# SCH_power_LED_2026-05-29.net
KiCad netlist of a schematic drawn in EasyEDA
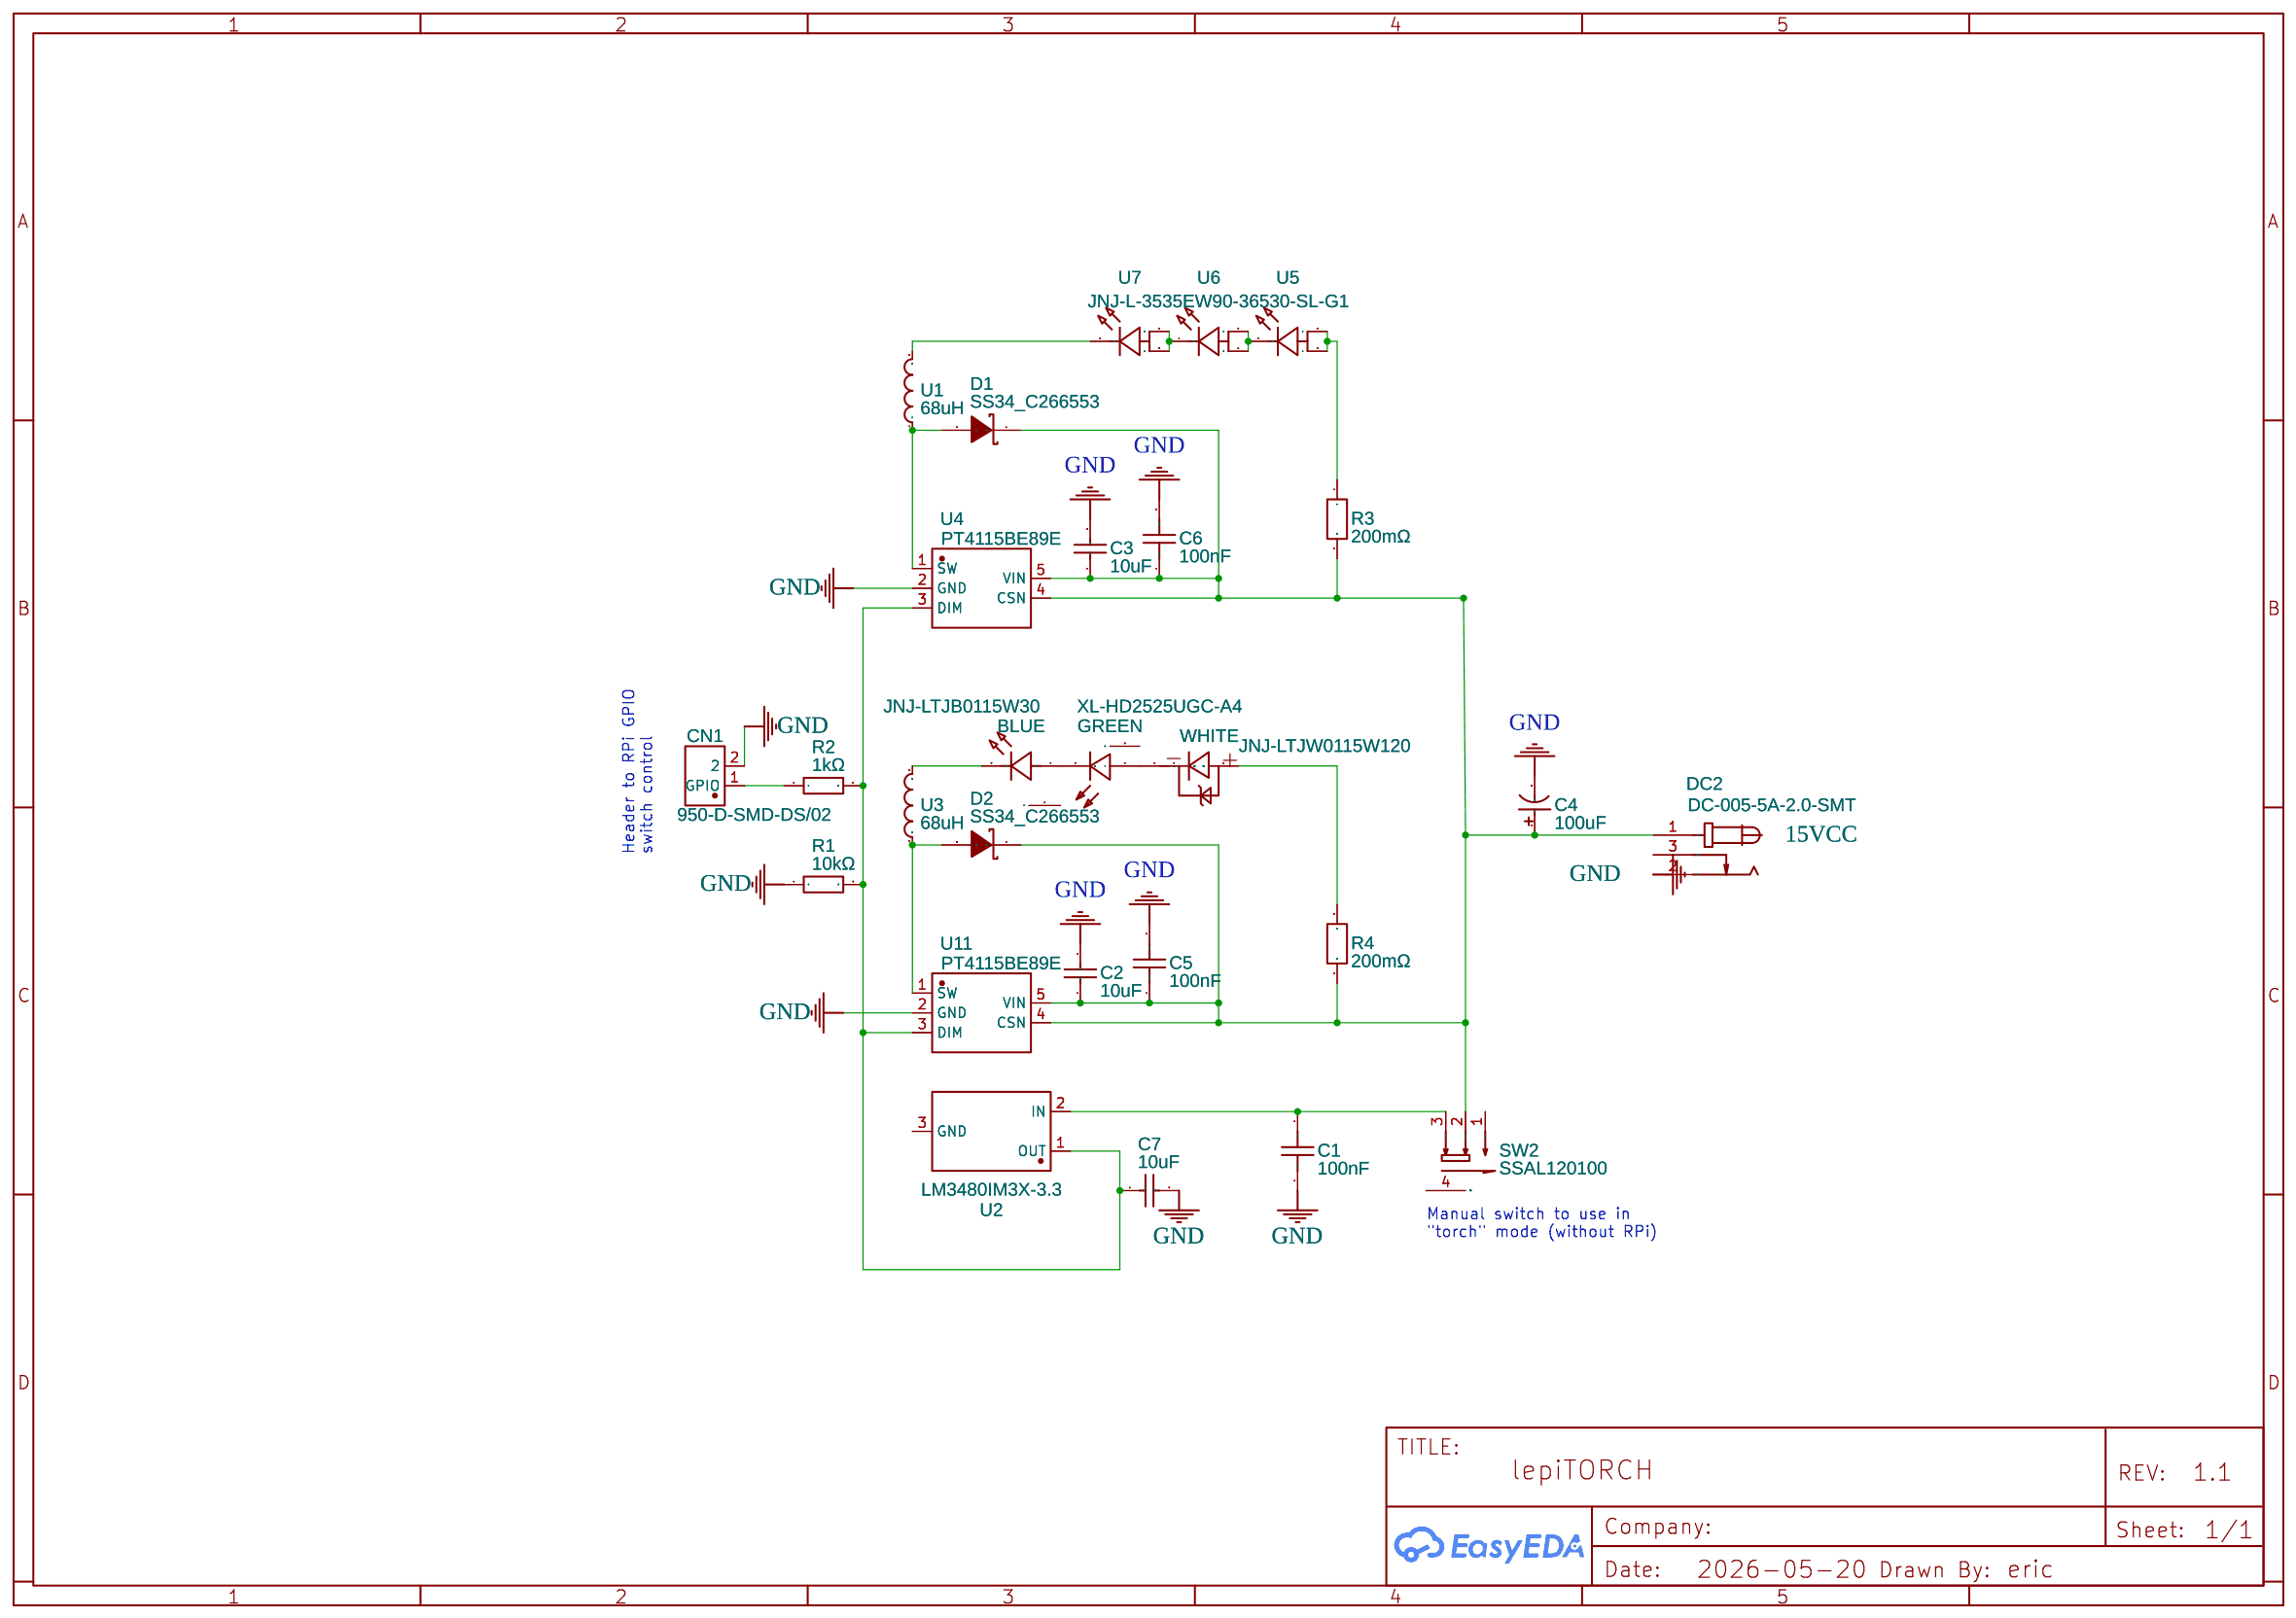
[diagram p0: schematic sheet]

(export (version "E")
  (design (tool "Eeschema 10.0.6"))
  (components
    (comp (ref "BLUE")
      (value "JNJ-LTJB0115W30")
      (fields
        (field (name "Manufacturer Part") "JNJ-LTJB0115W30/56mil/450-460nm")
        (field (name "Manufacturer") "JNJOPTO(强生光电)")
      )
      (libsource (lib "") (part "JNJ-LTJB0115W30/56MIL/450-460NM"))
    )
    (comp (ref "C1")
      (value "100nF")
      (fields (field (name "Manufacturer Part") "GMC04X7R104K25NT") (field (name "Manufacturer") "CAL-CHIP"))
      (libsource (lib "") (part "GMC04X7R104K25NT"))
    )
    (comp (ref "C2")
      (value "10uF")
      (fields
        (field (name "Manufacturer Part") "GRM31CR71E106KA12L")
        (field (name "Manufacturer") "muRata(村田)")
      )
      (libsource (lib "") (part "GRM31CR71E106KA12L"))
    )
    (comp (ref "C3")
      (value "10uF")
      (fields
        (field (name "Manufacturer Part") "GRM31CR71E106KA12L")
        (field (name "Manufacturer") "muRata(村田)")
      )
      (libsource (lib "") (part "GRM31CR71E106KA12L"))
    )
    (comp (ref "C4")
      (value "100uF")
      (fields (field (name "Manufacturer Part") "RVT1E101M0607") (field (name "Manufacturer") "HONOR(荣誉)"))
      (libsource (lib "") (part "RVT1E101M0607"))
    )
    (comp (ref "C5")
      (value "100nF")
      (fields (field (name "Manufacturer Part") "GMC04X7R104K25NT") (field (name "Manufacturer") "CAL-CHIP"))
      (libsource (lib "") (part "GMC04X7R104K25NT"))
    )
    (comp (ref "C6")
      (value "100nF")
      (fields (field (name "Manufacturer Part") "GMC04X7R104K25NT") (field (name "Manufacturer") "CAL-CHIP"))
      (libsource (lib "") (part "GMC04X7R104K25NT"))
    )
    (comp (ref "C7")
      (value "10uF")
      (fields
        (field (name "Manufacturer Part") "GRM31CR71E106KA12L")
        (field (name "Manufacturer") "muRata(村田)")
      )
      (libsource (lib "") (part "GRM31CR71E106KA12L_1"))
    )
    (comp (ref "CN1")
      (value "950-D-SMD-DS/02")
      (fields (field (name "Manufacturer") "WECO(威克德诺)"))
      (libsource (lib "") (part "950-D-SMD-DS/02"))
    )
    (comp (ref "D1")
      (value "SS34_C266553")
      (fields (field (name "Manufacturer Part") "SS34") (field (name "Manufacturer") "BORN(伯恩半导体)"))
      (libsource (lib "") (part "SS34_C266553"))
    )
    (comp (ref "D2")
      (value "SS34_C266553")
      (fields (field (name "Manufacturer Part") "SS34") (field (name "Manufacturer") "BORN(伯恩半导体)"))
      (libsource (lib "") (part "SS34_C266553"))
    )
    (comp (ref "DC2")
      (value "DC-005-5A-2.0-SMT")
      (fields (field (name "Manufacturer") "XKB Connection(中国星坤)"))
      (libsource (lib "") (part "DC-005-5A-2.0-SMT"))
    )
    (comp (ref "GREEN")
      (value "XL-HD2525UGC-A4")
      (fields (field (name "Manufacturer") "XINGLIGHT(成兴光)"))
      (libsource (lib "") (part "XL-HD2525UGC-A4"))
    )
    (comp (ref "R1")
      (value "10kΩ")
      (fields
        (field (name "Manufacturer Part") "TR0402D10K0Q1025Z")
        (field (name "Manufacturer") "EVER OHMS(天二科技)")
      )
      (libsource (lib "") (part "TR0402D10KQ1025"))
    )
    (comp (ref "R2")
      (value "1kΩ")
      (fields
        (field (name "Manufacturer Part") "QR0402F1K00Q10Z")
        (field (name "Manufacturer") "EVER OHMS(天二科技)")
      )
      (libsource (lib "") (part "QR0402F1KQ10"))
    )
    (comp (ref "R3")
      (value "200mΩ")
      (fields (field (name "Manufacturer Part") "FRL0603FR200TS") (field (name "Manufacturer") "FOJAN(富捷)"))
      (libsource (lib "") (part "FRL0603FR200TS"))
    )
    (comp (ref "R4")
      (value "200mΩ")
      (fields (field (name "Manufacturer Part") "FRL0603FR200TS") (field (name "Manufacturer") "FOJAN(富捷)"))
      (libsource (lib "") (part "FRL0603FR200TS"))
    )
    (comp (ref "SW2")
      (value "SSAL120100")
      (fields (field (name "Manufacturer") "ALPSALPINE(阿尔卑斯阿尔派)"))
      (libsource (lib "") (part "SSAL120100"))
    )
    (comp (ref "U1")
      (value "68uH")
      (fields (field (name "Manufacturer Part") "CYA0650-68UH") (field (name "Manufacturer") "SHOU HAN(首韩)"))
      (libsource (lib "") (part "CYA0650-68UH"))
    )
    (comp (ref "U2")
      (value "LM3480IM3X-3.3")
      (fields (field (name "Manufacturer") "TI(德州仪器)"))
      (libsource (lib "") (part "LM3480IM3X-3.3"))
    )
    (comp (ref "U3")
      (value "68uH")
      (fields (field (name "Manufacturer Part") "CYA0650-68UH") (field (name "Manufacturer") "SHOU HAN(首韩)"))
      (libsource (lib "") (part "CYA0650-68UH"))
    )
    (comp (ref "U4")
      (value "PT4115BE89E")
      (fields (field (name "Manufacturer") "PowTech(华润矽威)"))
      (libsource (lib "") (part "PT4115BE89E"))
    )
    (comp (ref "U5")
      (value "JNJ-L-3535EW90-36530-SL-G1")
      (fields (field (name "Manufacturer") "JNJOPTO(强生光电)"))
      (libsource (lib "") (part "JNJ-L-3535EW90-36530-SL-G1"))
    )
    (comp (ref "U6")
      (value "JNJ-L-3535EW90-36530-SL-G1")
      (fields (field (name "Manufacturer") "JNJOPTO(强生光电)"))
      (libsource (lib "") (part "JNJ-L-3535EW90-36530-SL-G1"))
    )
    (comp (ref "U7")
      (value "JNJ-L-3535EW90-36530-SL-G1")
      (fields (field (name "Manufacturer") "JNJOPTO(强生光电)"))
      (libsource (lib "") (part "JNJ-L-3535EW90-36530-SL-G1"))
    )
    (comp (ref "U11")
      (value "PT4115BE89E")
      (fields (field (name "Manufacturer") "PowTech(华润矽威)"))
      (libsource (lib "") (part "PT4115BE89E"))
    )
    (comp (ref "WHITE")
      (value "JNJ-LTJW0115W120")
      (fields
        (field (name "Manufacturer Part") "JNJ-LTJW0115W120/63MIL/6500-7000K")
        (field (name "Manufacturer") "JNJOPTO(强生光电)")
      )
      (libsource (lib "") (part "JNJ-LTJW0115W120/63MIL/6500-7000K"))
    )
  )
  (nets
    (net (code "2") (name "GND") (class "Default")
      (node (ref "C1") (pin "1") (pinfunction "1_1") (pintype "unspecified"))
      (node (ref "C2") (pin "2") (pinfunction "2_2") (pintype "input"))
      (node (ref "C3") (pin "2") (pinfunction "2_2") (pintype "input"))
      (node (ref "C4") (pin "2") (pinfunction "2_2") (pintype "input"))
      (node (ref "C5") (pin "2") (pinfunction "2_2") (pintype "unspecified"))
      (node (ref "C6") (pin "2") (pinfunction "2_2") (pintype "unspecified"))
      (node (ref "C7") (pin "2") (pinfunction "2_2") (pintype "input"))
      (node (ref "CN1") (pin "2") (pinfunction "2_2") (pintype "unspecified"))
      (node (ref "DC2") (pin "2") (pinfunction "2_2") (pintype "unspecified"))
      (node (ref "R1") (pin "1") (pinfunction "1_1") (pintype "unspecified"))
      (node (ref "U11") (pin "2") (pinfunction "GND_2") (pintype "unspecified"))
      (node (ref "U4") (pin "2") (pinfunction "GND_2") (pintype "unspecified"))
    )
    (net (code "3") (name "Net-(BLUE-K)") (class "Default")
      (node (ref "BLUE") (pin "2") (pinfunction "K_2") (pintype "unspecified"))
      (node (ref "U3") (pin "2") (pinfunction "2_2") (pintype "unspecified"))
    )
    (net (code "4") (name "Net-(CN1-GPIO)") (class "Default")
      (node (ref "CN1") (pin "1") (pinfunction "GPIO_1") (pintype "unspecified"))
      (node (ref "R2") (pin "1") (pinfunction "1_1") (pintype "unspecified"))
    )
    (net (code "5") (name "Net-(D1-A)") (class "Default")
      (node (ref "D1") (pin "2") (pinfunction "A_2") (pintype "unspecified"))
      (node (ref "U1") (pin "1") (pinfunction "1_1") (pintype "unspecified"))
      (node (ref "U4") (pin "1") (pinfunction "SW_1") (pintype "unspecified"))
    )
    (net (code "6") (name "Net-(D1-C)") (class "Default")
      (node (ref "C2") (pin "1") (pinfunction "1_1") (pintype "input"))
      (node (ref "C3") (pin "1") (pinfunction "1_1") (pintype "input"))
      (node (ref "C4") (pin "1") (pinfunction "1_1") (pintype "input"))
      (node (ref "C5") (pin "1") (pinfunction "1_1") (pintype "unspecified"))
      (node (ref "C6") (pin "1") (pinfunction "1_1") (pintype "unspecified"))
      (node (ref "D1") (pin "1") (pinfunction "C_1") (pintype "unspecified"))
      (node (ref "D2") (pin "1") (pinfunction "C_1") (pintype "unspecified"))
      (node (ref "DC2") (pin "1") (pinfunction "1_1") (pintype "unspecified"))
      (node (ref "R3") (pin "2") (pinfunction "2_2") (pintype "unspecified"))
      (node (ref "R4") (pin "2") (pinfunction "2_2") (pintype "unspecified"))
      (node (ref "SW2") (pin "2") (pinfunction "2_2") (pintype "unspecified"))
      (node (ref "U11") (pin "4") (pinfunction "CSN_4") (pintype "unspecified"))
      (node (ref "U11") (pin "5") (pinfunction "VIN_5") (pintype "unspecified"))
      (node (ref "U4") (pin "4") (pinfunction "CSN_4") (pintype "unspecified"))
      (node (ref "U4") (pin "5") (pinfunction "VIN_5") (pintype "unspecified"))
    )
    (net (code "7") (name "Net-(D2-A)") (class "Default")
      (node (ref "D2") (pin "2") (pinfunction "A_2") (pintype "unspecified"))
      (node (ref "U11") (pin "1") (pinfunction "SW_1") (pintype "unspecified"))
      (node (ref "U3") (pin "1") (pinfunction "1_1") (pintype "unspecified"))
    )
    (net (code "8") (name "Net-(GREEN-A)") (class "Default")
      (node (ref "GREEN") (pin "2") (pinfunction "A_2") (pintype "unspecified"))
      (node (ref "WHITE") (pin "1") (pinfunction "Cathode_1") (pintype "unspecified"))
    )
    (net (code "9") (name "Net-(GREEN-C)") (class "Default")
      (node (ref "BLUE") (pin "1") (pinfunction "A_1") (pintype "unspecified"))
      (node (ref "GREEN") (pin "1") (pinfunction "C_1") (pintype "unspecified"))
    )
    (net (code "10") (name "Net-(R3-Pad1)") (class "Default")
      (node (ref "R3") (pin "1") (pinfunction "1_1") (pintype "unspecified"))
      (node (ref "U5") (pin "2") (pinfunction "A_2") (pintype "unspecified"))
      (node (ref "U5") (pin "3") (pinfunction "A_3") (pintype "unspecified"))
    )
    (net (code "11") (name "Net-(U2-IN)") (class "Default")
      (node (ref "C1") (pin "2") (pinfunction "2_2") (pintype "unspecified"))
      (node (ref "SW2") (pin "3") (pinfunction "3_3") (pintype "unspecified"))
      (node (ref "U2") (pin "2") (pinfunction "IN_2") (pintype "unspecified"))
    )
    (net (code "12") (name "Net-(U5-C)") (class "Default")
      (node (ref "U5") (pin "1") (pinfunction "C_1") (pintype "unspecified"))
      (node (ref "U6") (pin "2") (pinfunction "A_2") (pintype "unspecified"))
      (node (ref "U6") (pin "3") (pinfunction "A_3") (pintype "unspecified"))
    )
    (net (code "13") (name "Net-(U6-C)") (class "Default")
      (node (ref "U6") (pin "1") (pinfunction "C_1") (pintype "unspecified"))
      (node (ref "U7") (pin "2") (pinfunction "A_2") (pintype "unspecified"))
      (node (ref "U7") (pin "3") (pinfunction "A_3") (pintype "unspecified"))
    )
    (net (code "14") (name "Net-(U7-C)") (class "Default")
      (node (ref "U1") (pin "2") (pinfunction "2_2") (pintype "unspecified"))
      (node (ref "U7") (pin "1") (pinfunction "C_1") (pintype "unspecified"))
    )
    (net (code "15") (name "Net-(U11-DIM)") (class "Default")
      (node (ref "C7") (pin "1") (pinfunction "1_1") (pintype "input"))
      (node (ref "R1") (pin "2") (pinfunction "2_2") (pintype "unspecified"))
      (node (ref "R2") (pin "2") (pinfunction "2_2") (pintype "unspecified"))
      (node (ref "U11") (pin "3") (pinfunction "DIM_3") (pintype "unspecified"))
      (node (ref "U2") (pin "1") (pinfunction "OUT_1") (pintype "unspecified"))
      (node (ref "U4") (pin "3") (pinfunction "DIM_3") (pintype "unspecified"))
    )
    (net (code "16") (name "Net-(WHITE-Anode)") (class "Default")
      (node (ref "R4") (pin "1") (pinfunction "1_1") (pintype "unspecified"))
      (node (ref "WHITE") (pin "3") (pinfunction "Anode_3") (pintype "unspecified"))
    )
    (net (code "17") (name "unconnected-(BLUE-A-Pad3)") (class "Default")
      (node (ref "BLUE") (pin "3") (pinfunction "A_3") (pintype "unspecified"))
    )
    (net (code "18") (name "unconnected-(DC2-Pad3)") (class "Default")
      (node (ref "DC2") (pin "3") (pinfunction "3_3") (pintype "unspecified"))
    )
    (net (code "19") (name "unconnected-(GREEN-Pad3)") (class "Default")
      (node (ref "GREEN") (pin "3") (pinfunction "3_3") (pintype "unspecified"))
    )
    (net (code "20") (name "unconnected-(SW2-Pad1)") (class "Default")
      (node (ref "SW2") (pin "1") (pinfunction "1_1") (pintype "unspecified"))
    )
    (net (code "21") (name "unconnected-(SW2-SHELL-Pad4)") (class "Default")
      (node (ref "SW2") (pin "4") (pinfunction "SHELL_4") (pintype "unspecified"))
    )
    (net (code "22") (name "unconnected-(U2-GND-Pad3)") (class "Default")
      (node (ref "U2") (pin "3") (pinfunction "GND_3") (pintype "unspecified"))
    )
    (net (code "23") (name "unconnected-(WHITE-Cathode-Pad2)") (class "Default")
      (node (ref "WHITE") (pin "2") (pinfunction "Cathode_2") (pintype "unspecified"))
    )
  )
)
